# transmisorPCB_2_0.net
KiCad netlist of a schematic drawn in EAGLE
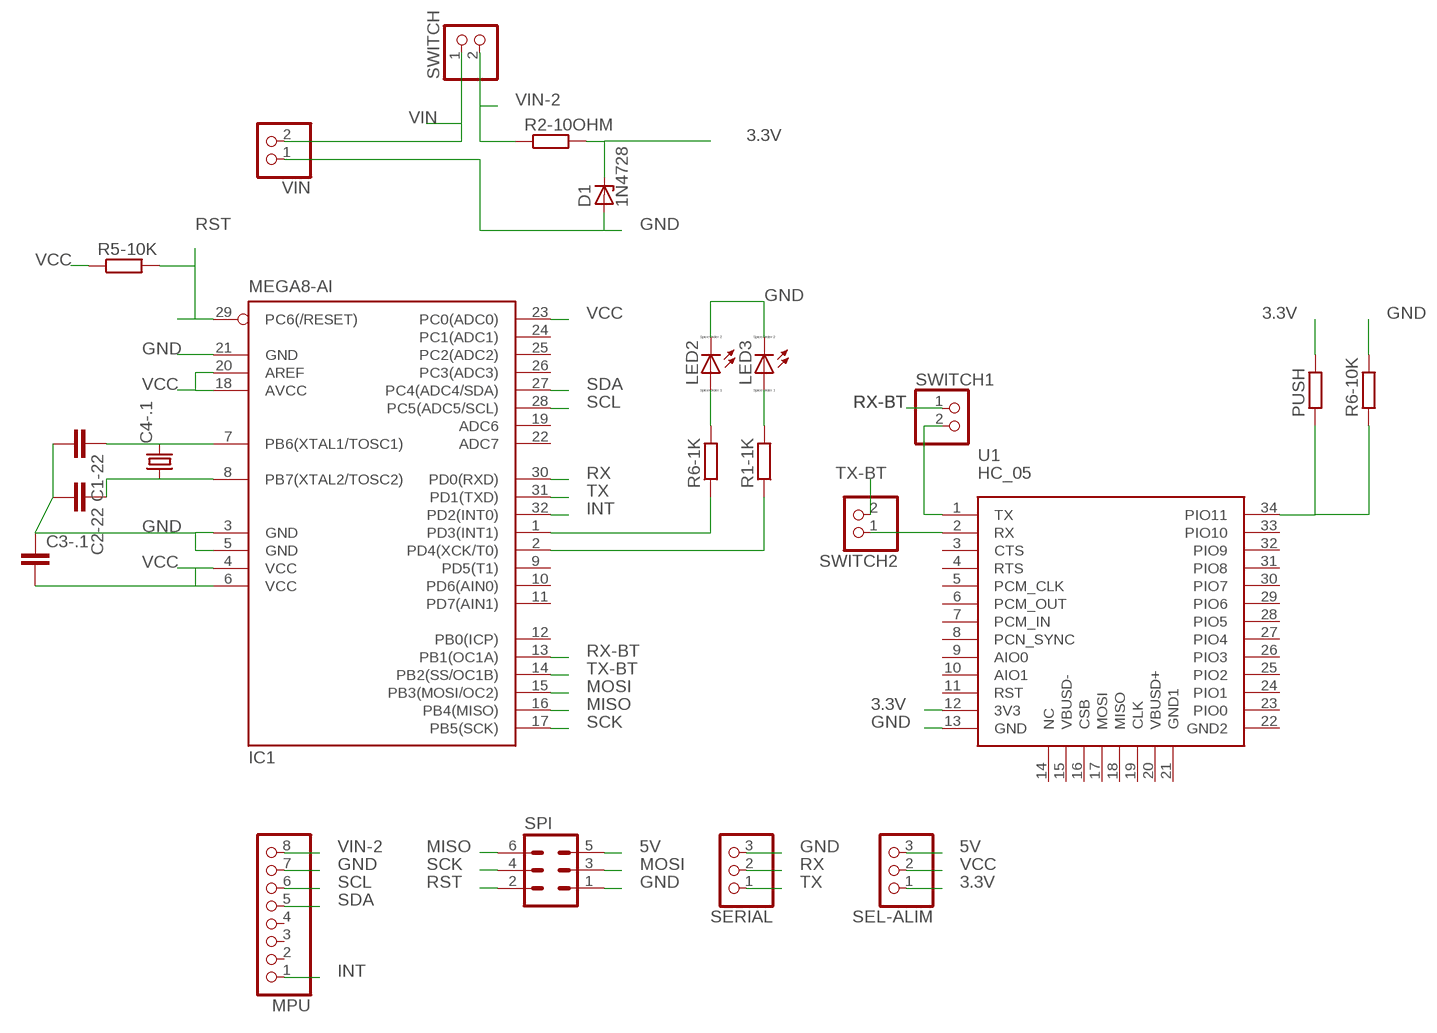
[diagram p0: schematic, sheet 1]

(export (version "E")
  (design (tool "Eeschema 10.0.6"))
  (components
    (comp (ref "C1-22")
      (value "C-EUC0402K")
      (footprint "eagle-import:C0402K")
      (libsource (lib "eagle-import") (part "C-EUC0402K"))
    )
    (comp (ref "C2-22")
      (value "C-EUC0402K")
      (footprint "eagle-import:C0402K")
      (libsource (lib "eagle-import") (part "C-EUC0402K"))
    )
    (comp (ref "C3-.1")
      (value "C-EUC0402K")
      (footprint "eagle-import:C0402K")
      (libsource (lib "eagle-import") (part "C-EUC0402K"))
    )
    (comp (ref "C4-.1")
      (value "CRYSTALHC49U70")
      (footprint "eagle-import:HC49U70")
      (libsource (lib "eagle-import") (part "CRYSTALHC49U70"))
    )
    (comp (ref "D1")
      (value "1N4728")
      (footprint "eagle-import:DO41Z10")
      (libsource (lib "eagle-import") (part "1N4728"))
    )
    (comp (ref "IC1")
      (value "MEGA8-AI")
      (footprint "eagle-import:TQFP32-08")
      (fields (field (name "MPN") "ATMEGA8-16AU"))
      (libsource (lib "eagle-import") (part "MEGA8-AI"))
    )
    (comp (ref "LED2")
      (value "LED_ESML0603")
      (footprint "eagle-import:LED_SML0603")
      (libsource (lib "eagle-import") (part "LED_ESML0603"))
    )
    (comp (ref "LED3")
      (value "LED_ESML0603")
      (footprint "eagle-import:LED_SML0603")
      (libsource (lib "eagle-import") (part "LED_ESML0603"))
    )
    (comp (ref "MPU")
      (value "PINHD-1X8")
      (footprint "eagle-import:1X08")
      (libsource (lib "eagle-import") (part "PINHD-1X8"))
    )
    (comp (ref "PUSH")
      (value "R-EU_M2309")
      (footprint "eagle-import:M2309")
      (libsource (lib "eagle-import") (part "R-EU_M2309"))
    )
    (comp (ref "R1-1K")
      (value "R-EU_M1206")
      (footprint "eagle-import:M1206")
      (libsource (lib "eagle-import") (part "R-EU_M1206"))
    )
    (comp (ref "R2-10OHM")
      (value "R-EU_R2512")
      (footprint "eagle-import:R2512")
      (libsource (lib "eagle-import") (part "resistor_R-EU_R2512"))
    )
    (comp (ref "R5-10K")
      (value "R-EU_M1206")
      (footprint "eagle-import:M1206")
      (libsource (lib "eagle-import") (part "R-EU_M1206"))
    )
    (comp (ref "R6-1K")
      (value "R-EU_M1206")
      (footprint "eagle-import:M1206")
      (libsource (lib "eagle-import") (part "R-EU_M1206"))
    )
    (comp (ref "R6-10K")
      (value "R-EU_M1206")
      (footprint "eagle-import:M1206")
      (libsource (lib "eagle-import") (part "R-EU_M1206"))
    )
    (comp (ref "SEL-ALIM")
      (value "PINHD-1X3")
      (footprint "eagle-import:1X03")
      (libsource (lib "eagle-import") (part "PINHD-1X3"))
    )
    (comp (ref "SERIAL")
      (value "PINHD-1X3")
      (footprint "eagle-import:1X03")
      (libsource (lib "eagle-import") (part "PINHD-1X3"))
    )
    (comp (ref "SPI")
      (value "MA03-2")
      (footprint "eagle-import:MA03-2")
      (libsource (lib "eagle-import") (part "MA03-2"))
    )
    (comp (ref "SWITCH")
      (value "PINHD-1X2")
      (footprint "eagle-import:1X02")
      (libsource (lib "eagle-import") (part "PINHD-1X2"))
    )
    (comp (ref "SWITCH1")
      (value "PINHD-1X2")
      (footprint "eagle-import:1X02")
      (libsource (lib "eagle-import") (part "PINHD-1X2"))
    )
    (comp (ref "SWITCH2")
      (value "PINHD-1X2")
      (footprint "eagle-import:1X02")
      (libsource (lib "eagle-import") (part "PINHD-1X2"))
    )
    (comp (ref "U1")
      (value "HC_05")
      (footprint "eagle-import:BLUETOOTH_SMD")
      (libsource (lib "eagle-import") (part "HC_05"))
    )
    (comp (ref "VIN")
      (value "PINHD-1X2")
      (footprint "eagle-import:1X02")
      (libsource (lib "eagle-import") (part "PINHD-1X2"))
    )
  )
  (nets
    (net (code "1") (name "/3.3V") (class "Default")
      (node (ref "D1") (pin "C") (pinfunction "C_C") (pintype "passive"))
      (node (ref "PUSH") (pin "2") (pinfunction "2_2") (pintype "passive"))
      (node (ref "R2-10OHM") (pin "2") (pinfunction "2_2") (pintype "passive"))
      (node (ref "SEL-ALIM") (pin "1") (pinfunction "1_1") (pintype "passive"))
      (node (ref "U1") (pin "12") (pinfunction "3V3_12") (pintype "bidirectional"))
    )
    (net (code "2") (name "/5V") (class "Default")
      (node (ref "SEL-ALIM") (pin "3") (pinfunction "3_3") (pintype "passive"))
      (node (ref "SPI") (pin "5") (pinfunction "5_5") (pintype "passive"))
    )
    (net (code "3") (name "/GND") (class "Default")
      (node (ref "C1-22") (pin "2") (pinfunction "2_2") (pintype "passive"))
      (node (ref "C2-22") (pin "2") (pinfunction "2_2") (pintype "passive"))
      (node (ref "C3-.1") (pin "1") (pinfunction "1_1") (pintype "passive"))
      (node (ref "D1") (pin "A") (pinfunction "A_A") (pintype "passive"))
      (node (ref "IC1") (pin "21") (pinfunction "GND_21") (pintype "power_in"))
      (node (ref "IC1") (pin "3") (pinfunction "GND_3") (pintype "power_in"))
      (node (ref "IC1") (pin "5") (pinfunction "GND_5") (pintype "power_in"))
      (node (ref "LED2") (pin "C") (pinfunction "C_C") (pintype "passive"))
      (node (ref "LED3") (pin "C") (pinfunction "C_C") (pintype "passive"))
      (node (ref "MPU") (pin "7") (pinfunction "7_7") (pintype "passive"))
      (node (ref "R6-10K") (pin "2") (pinfunction "2_2") (pintype "passive"))
      (node (ref "SERIAL") (pin "3") (pinfunction "3_3") (pintype "passive"))
      (node (ref "SPI") (pin "1") (pinfunction "1_1") (pintype "passive"))
      (node (ref "U1") (pin "13") (pinfunction "GND_13") (pintype "bidirectional"))
      (node (ref "VIN") (pin "1") (pinfunction "1_1") (pintype "passive"))
    )
    (net (code "4") (name "/INT") (class "Default")
      (node (ref "IC1") (pin "32") (pinfunction "PD2(INT0)_32") (pintype "bidirectional"))
      (node (ref "MPU") (pin "1") (pinfunction "1_1") (pintype "passive"))
    )
    (net (code "5") (name "/MISO") (class "Default")
      (node (ref "IC1") (pin "16") (pinfunction "PB4(MISO)_16") (pintype "bidirectional"))
      (node (ref "SPI") (pin "6") (pinfunction "6_6") (pintype "passive"))
    )
    (net (code "6") (name "/MOSI") (class "Default")
      (node (ref "IC1") (pin "15") (pinfunction "PB3(MOSI/OC2)_15") (pintype "bidirectional"))
      (node (ref "SPI") (pin "3") (pinfunction "3_3") (pintype "passive"))
    )
    (net (code "7") (name "/RST") (class "Default")
      (node (ref "IC1") (pin "29") (pinfunction "PC6(/RESET)_29") (pintype "bidirectional"))
      (node (ref "R5-10K") (pin "2") (pinfunction "2_2") (pintype "passive"))
      (node (ref "SPI") (pin "2") (pinfunction "2_2") (pintype "passive"))
    )
    (net (code "8") (name "/RX") (class "Default")
      (node (ref "IC1") (pin "30") (pinfunction "PD0(RXD)_30") (pintype "bidirectional"))
      (node (ref "SERIAL") (pin "2") (pinfunction "2_2") (pintype "passive"))
    )
    (net (code "9") (name "/RX-BT") (class "Default")
      (node (ref "IC1") (pin "13") (pinfunction "PB1(OC1A)_13") (pintype "bidirectional"))
      (node (ref "SWITCH1") (pin "1") (pinfunction "1_1") (pintype "passive"))
    )
    (net (code "10") (name "/SCK") (class "Default")
      (node (ref "IC1") (pin "17") (pinfunction "PB5(SCK)_17") (pintype "bidirectional"))
      (node (ref "SPI") (pin "4") (pinfunction "4_4") (pintype "passive"))
    )
    (net (code "11") (name "/SCL") (class "Default")
      (node (ref "IC1") (pin "28") (pinfunction "PC5(ADC5/SCL)_28") (pintype "bidirectional"))
      (node (ref "MPU") (pin "6") (pinfunction "6_6") (pintype "passive"))
    )
    (net (code "12") (name "/SDA") (class "Default")
      (node (ref "IC1") (pin "27") (pinfunction "PC4(ADC4/SDA)_27") (pintype "bidirectional"))
      (node (ref "MPU") (pin "5") (pinfunction "5_5") (pintype "passive"))
    )
    (net (code "13") (name "/TX") (class "Default")
      (node (ref "IC1") (pin "31") (pinfunction "PD1(TXD)_31") (pintype "bidirectional"))
      (node (ref "SERIAL") (pin "1") (pinfunction "1_1") (pintype "passive"))
    )
    (net (code "14") (name "/TX-BT") (class "Default")
      (node (ref "IC1") (pin "14") (pinfunction "PB2(SS/OC1B)_14") (pintype "bidirectional"))
      (node (ref "SWITCH2") (pin "2") (pinfunction "2_2") (pintype "passive"))
    )
    (net (code "15") (name "/VCC") (class "Default")
      (node (ref "C3-.1") (pin "2") (pinfunction "2_2") (pintype "passive"))
      (node (ref "IC1") (pin "18") (pinfunction "AVCC_18") (pintype "power_in"))
      (node (ref "IC1") (pin "20") (pinfunction "AREF_20") (pintype "passive"))
      (node (ref "IC1") (pin "23") (pinfunction "PC0(ADC0)_23") (pintype "bidirectional"))
      (node (ref "IC1") (pin "4") (pinfunction "VCC_4") (pintype "power_in"))
      (node (ref "IC1") (pin "6") (pinfunction "VCC_6") (pintype "power_in"))
      (node (ref "R5-10K") (pin "1") (pinfunction "1_1") (pintype "passive"))
      (node (ref "SEL-ALIM") (pin "2") (pinfunction "2_2") (pintype "passive"))
    )
    (net (code "16") (name "/VIN") (class "Default")
      (node (ref "SWITCH") (pin "1") (pinfunction "1_1") (pintype "passive"))
      (node (ref "VIN") (pin "2") (pinfunction "2_2") (pintype "passive"))
    )
    (net (code "17") (name "/VIN-2") (class "Default")
      (node (ref "MPU") (pin "8") (pinfunction "8_8") (pintype "passive"))
      (node (ref "R2-10OHM") (pin "1") (pinfunction "1_1") (pintype "passive"))
      (node (ref "SWITCH") (pin "2") (pinfunction "2_2") (pintype "passive"))
    )
    (net (code "18") (name "Net-(IC1-PB6(XTAL1{slash}TOSC1))") (class "Default")
      (node (ref "C1-22") (pin "1") (pinfunction "1_1") (pintype "passive"))
      (node (ref "C4-.1") (pin "2") (pinfunction "2_2") (pintype "passive"))
      (node (ref "IC1") (pin "7") (pinfunction "PB6(XTAL1/TOSC1)_7") (pintype "bidirectional"))
    )
    (net (code "19") (name "Net-(IC1-PB7(XTAL2{slash}TOSC2))") (class "Default")
      (node (ref "C2-22") (pin "1") (pinfunction "1_1") (pintype "passive"))
      (node (ref "C4-.1") (pin "1") (pinfunction "1_1") (pintype "passive"))
      (node (ref "IC1") (pin "8") (pinfunction "PB7(XTAL2/TOSC2)_8") (pintype "bidirectional"))
    )
    (net (code "20") (name "Net-(IC1-PD3(INT1))") (class "Default")
      (node (ref "IC1") (pin "1") (pinfunction "PD3(INT1)_1") (pintype "bidirectional"))
      (node (ref "R6-1K") (pin "1") (pinfunction "1_1") (pintype "passive"))
    )
    (net (code "21") (name "Net-(IC1-PD4(XCK{slash}T0))") (class "Default")
      (node (ref "IC1") (pin "2") (pinfunction "PD4(XCK/T0)_2") (pintype "bidirectional"))
      (node (ref "R1-1K") (pin "1") (pinfunction "1_1") (pintype "passive"))
    )
    (net (code "22") (name "Net-(LED2-PadA)") (class "Default")
      (node (ref "LED2") (pin "A") (pinfunction "A_A") (pintype "passive"))
      (node (ref "R6-1K") (pin "2") (pinfunction "2_2") (pintype "passive"))
    )
    (net (code "23") (name "Net-(LED3-PadA)") (class "Default")
      (node (ref "LED3") (pin "A") (pinfunction "A_A") (pintype "passive"))
      (node (ref "R1-1K") (pin "2") (pinfunction "2_2") (pintype "passive"))
    )
    (net (code "24") (name "Net-(U1-PIO11)") (class "Default")
      (node (ref "PUSH") (pin "1") (pinfunction "1_1") (pintype "passive"))
      (node (ref "R6-10K") (pin "1") (pinfunction "1_1") (pintype "passive"))
      (node (ref "U1") (pin "34") (pinfunction "PIO11_34") (pintype "bidirectional"))
    )
    (net (code "25") (name "Net-(U1-RX)") (class "Default")
      (node (ref "SWITCH2") (pin "1") (pinfunction "1_1") (pintype "passive"))
      (node (ref "U1") (pin "2") (pinfunction "RX_2") (pintype "bidirectional"))
    )
    (net (code "26") (name "Net-(U1-TX)") (class "Default")
      (node (ref "SWITCH1") (pin "2") (pinfunction "2_2") (pintype "passive"))
      (node (ref "U1") (pin "1") (pinfunction "TX_1") (pintype "bidirectional"))
    )
    (net (code "27") (name "unconnected-(IC1-ADC6-Pad19)") (class "Default")
      (node (ref "IC1") (pin "19") (pinfunction "ADC6_19") (pintype "bidirectional"))
    )
    (net (code "28") (name "unconnected-(IC1-ADC7-Pad22)") (class "Default")
      (node (ref "IC1") (pin "22") (pinfunction "ADC7_22") (pintype "bidirectional"))
    )
    (net (code "29") (name "unconnected-(IC1-PB0(ICP)-Pad12)") (class "Default")
      (node (ref "IC1") (pin "12") (pinfunction "PB0(ICP)_12") (pintype "bidirectional"))
    )
    (net (code "30") (name "unconnected-(IC1-PC1(ADC1)-Pad24)") (class "Default")
      (node (ref "IC1") (pin "24") (pinfunction "PC1(ADC1)_24") (pintype "bidirectional"))
    )
    (net (code "31") (name "unconnected-(IC1-PC2(ADC2)-Pad25)") (class "Default")
      (node (ref "IC1") (pin "25") (pinfunction "PC2(ADC2)_25") (pintype "bidirectional"))
    )
    (net (code "32") (name "unconnected-(IC1-PC3(ADC3)-Pad26)") (class "Default")
      (node (ref "IC1") (pin "26") (pinfunction "PC3(ADC3)_26") (pintype "bidirectional"))
    )
    (net (code "33") (name "unconnected-(IC1-PD5(T1)-Pad9)") (class "Default")
      (node (ref "IC1") (pin "9") (pinfunction "PD5(T1)_9") (pintype "bidirectional"))
    )
    (net (code "34") (name "unconnected-(IC1-PD6(AIN0)-Pad10)") (class "Default")
      (node (ref "IC1") (pin "10") (pinfunction "PD6(AIN0)_10") (pintype "bidirectional"))
    )
    (net (code "35") (name "unconnected-(IC1-PD7(AIN1)-Pad11)") (class "Default")
      (node (ref "IC1") (pin "11") (pinfunction "PD7(AIN1)_11") (pintype "bidirectional"))
    )
    (net (code "36") (name "unconnected-(MPU-Pad2)") (class "Default")
      (node (ref "MPU") (pin "2") (pinfunction "2_2") (pintype "passive"))
    )
    (net (code "37") (name "unconnected-(MPU-Pad3)") (class "Default")
      (node (ref "MPU") (pin "3") (pinfunction "3_3") (pintype "passive"))
    )
    (net (code "38") (name "unconnected-(MPU-Pad4)") (class "Default")
      (node (ref "MPU") (pin "4") (pinfunction "4_4") (pintype "passive"))
    )
    (net (code "39") (name "unconnected-(U1-AIO0-Pad9)") (class "Default")
      (node (ref "U1") (pin "9") (pinfunction "AIO0_9") (pintype "bidirectional"))
    )
    (net (code "40") (name "unconnected-(U1-AIO1-Pad10)") (class "Default")
      (node (ref "U1") (pin "10") (pinfunction "AIO1_10") (pintype "bidirectional"))
    )
    (net (code "41") (name "unconnected-(U1-CLK-Pad19)") (class "Default")
      (node (ref "U1") (pin "19") (pinfunction "CLK_19") (pintype "bidirectional"))
    )
    (net (code "42") (name "unconnected-(U1-CSB-Pad16)") (class "Default")
      (node (ref "U1") (pin "16") (pinfunction "CSB_16") (pintype "bidirectional"))
    )
    (net (code "43") (name "unconnected-(U1-CTS-Pad3)") (class "Default")
      (node (ref "U1") (pin "3") (pinfunction "CTS_3") (pintype "bidirectional"))
    )
    (net (code "44") (name "unconnected-(U1-GND1-Pad21)") (class "Default")
      (node (ref "U1") (pin "21") (pinfunction "GND1_21") (pintype "bidirectional"))
    )
    (net (code "45") (name "unconnected-(U1-GND2-Pad22)") (class "Default")
      (node (ref "U1") (pin "22") (pinfunction "GND2_22") (pintype "bidirectional"))
    )
    (net (code "46") (name "unconnected-(U1-MISO-Pad18)") (class "Default")
      (node (ref "U1") (pin "18") (pinfunction "MISO_18") (pintype "bidirectional"))
    )
    (net (code "47") (name "unconnected-(U1-MOSI-Pad17)") (class "Default")
      (node (ref "U1") (pin "17") (pinfunction "MOSI_17") (pintype "bidirectional"))
    )
    (net (code "48") (name "unconnected-(U1-NC-Pad14)") (class "Default")
      (node (ref "U1") (pin "14") (pinfunction "NC_14") (pintype "bidirectional"))
    )
    (net (code "49") (name "unconnected-(U1-PCM_CLK-Pad5)") (class "Default")
      (node (ref "U1") (pin "5") (pinfunction "PCM_CLK_5") (pintype "bidirectional"))
    )
    (net (code "50") (name "unconnected-(U1-PCM_IN-Pad7)") (class "Default")
      (node (ref "U1") (pin "7") (pinfunction "PCM_IN_7") (pintype "bidirectional"))
    )
    (net (code "51") (name "unconnected-(U1-PCM_OUT-Pad6)") (class "Default")
      (node (ref "U1") (pin "6") (pinfunction "PCM_OUT_6") (pintype "bidirectional"))
    )
    (net (code "52") (name "unconnected-(U1-PCN_SYNC-Pad8)") (class "Default")
      (node (ref "U1") (pin "8") (pinfunction "PCN_SYNC_8") (pintype "bidirectional"))
    )
    (net (code "53") (name "unconnected-(U1-PIO0-Pad23)") (class "Default")
      (node (ref "U1") (pin "23") (pinfunction "PIO0_23") (pintype "bidirectional"))
    )
    (net (code "54") (name "unconnected-(U1-PIO1-Pad24)") (class "Default")
      (node (ref "U1") (pin "24") (pinfunction "PIO1_24") (pintype "bidirectional"))
    )
    (net (code "55") (name "unconnected-(U1-PIO2-Pad25)") (class "Default")
      (node (ref "U1") (pin "25") (pinfunction "PIO2_25") (pintype "bidirectional"))
    )
    (net (code "56") (name "unconnected-(U1-PIO3-Pad26)") (class "Default")
      (node (ref "U1") (pin "26") (pinfunction "PIO3_26") (pintype "bidirectional"))
    )
    (net (code "57") (name "unconnected-(U1-PIO4-Pad27)") (class "Default")
      (node (ref "U1") (pin "27") (pinfunction "PIO4_27") (pintype "bidirectional"))
    )
    (net (code "58") (name "unconnected-(U1-PIO5-Pad28)") (class "Default")
      (node (ref "U1") (pin "28") (pinfunction "PIO5_28") (pintype "bidirectional"))
    )
    (net (code "59") (name "unconnected-(U1-PIO6-Pad29)") (class "Default")
      (node (ref "U1") (pin "29") (pinfunction "PIO6_29") (pintype "bidirectional"))
    )
    (net (code "60") (name "unconnected-(U1-PIO7-Pad30)") (class "Default")
      (node (ref "U1") (pin "30") (pinfunction "PIO7_30") (pintype "bidirectional"))
    )
    (net (code "61") (name "unconnected-(U1-PIO8-Pad31)") (class "Default")
      (node (ref "U1") (pin "31") (pinfunction "PIO8_31") (pintype "bidirectional"))
    )
    (net (code "62") (name "unconnected-(U1-PIO9-Pad32)") (class "Default")
      (node (ref "U1") (pin "32") (pinfunction "PIO9_32") (pintype "bidirectional"))
    )
    (net (code "63") (name "unconnected-(U1-PIO10-Pad33)") (class "Default")
      (node (ref "U1") (pin "33") (pinfunction "PIO10_33") (pintype "bidirectional"))
    )
    (net (code "64") (name "unconnected-(U1-RST-Pad11)") (class "Default")
      (node (ref "U1") (pin "11") (pinfunction "RST_11") (pintype "bidirectional"))
    )
    (net (code "65") (name "unconnected-(U1-RTS-Pad4)") (class "Default")
      (node (ref "U1") (pin "4") (pinfunction "RTS_4") (pintype "bidirectional"))
    )
    (net (code "66") (name "unconnected-(U1-VBUSD+-Pad20)") (class "Default")
      (node (ref "U1") (pin "20") (pinfunction "VBUSD+_20") (pintype "bidirectional"))
    )
    (net (code "67") (name "unconnected-(U1-VBUSD--Pad15)") (class "Default")
      (node (ref "U1") (pin "15") (pinfunction "VBUSD-_15") (pintype "bidirectional"))
    )
  )
)
